# Zx81Composite.net
KiCad netlist of a schematic drawn in EAGLE
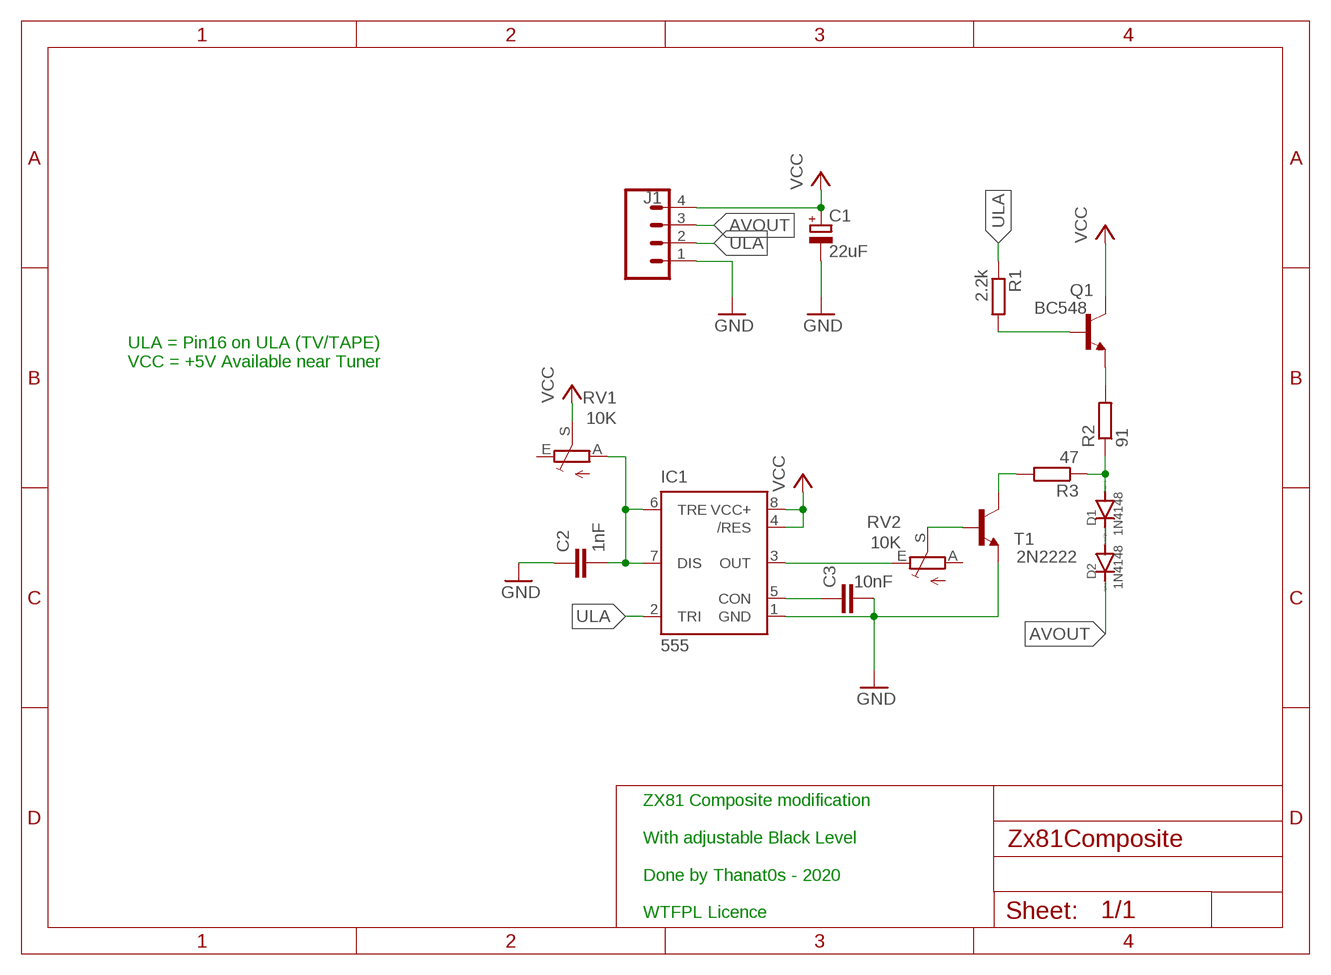
[diagram p0: schematic, sheet 1]

(export (version "E")
  (design (tool "Eeschema 10.0.6"))
  (components
    (comp (ref "C1")
      (value "22uF")
      (footprint "eagle-import:E2,5-5")
      (libsource (lib "eagle-import") (part "CPOL-EUE2.5-5"))
    )
    (comp (ref "C2")
      (value "1nF")
      (footprint "eagle-import:C025-024X044")
      (libsource (lib "eagle-import") (part "C-EU025-024X044"))
    )
    (comp (ref "C3")
      (value "10nF")
      (footprint "eagle-import:C025-024X044")
      (libsource (lib "eagle-import") (part "C-EU025-024X044"))
    )
    (comp (ref "D1")
      (value "1N4148")
      (footprint "eagle-import:DO35-7")
      (libsource (lib "eagle-import") (part "1N4148DO35-7"))
    )
    (comp (ref "D2")
      (value "1N4148")
      (footprint "eagle-import:DO35-7")
      (libsource (lib "eagle-import") (part "1N4148DO35-7"))
    )
    (comp (ref "IC1")
      (value "555")
      (footprint "eagle-import:DIP08")
      (libsource (lib "eagle-import") (part "555P"))
    )
    (comp (ref "J1")
      (value "CONN_04")
      (footprint "eagle-import:1X04")
      (libsource (lib "eagle-import") (part "CONN_04"))
    )
    (comp (ref "Q1")
      (value "BC548")
      (footprint "eagle-import:TO92-EBC")
      (libsource (lib "eagle-import") (part "BC548"))
    )
    (comp (ref "R1")
      (value "2.2k")
      (footprint "eagle-import:0207_7")
      (libsource (lib "eagle-import") (part "R-EU_0207/7"))
    )
    (comp (ref "R2")
      (value "91")
      (footprint "eagle-import:0207_7")
      (libsource (lib "eagle-import") (part "R-EU_0207/7"))
    )
    (comp (ref "R3")
      (value "47")
      (footprint "eagle-import:0207_7")
      (libsource (lib "eagle-import") (part "R-EU_0207/7"))
    )
    (comp (ref "RV1")
      (value "10K")
      (footprint "eagle-import:CA6V")
      (fields (field (name "SPICEPREFIX") "J"))
      (libsource (lib "eagle-import") (part "TRIM_EU-CA6V"))
    )
    (comp (ref "RV2")
      (value "10K")
      (footprint "eagle-import:CA6V")
      (fields (field (name "SPICEPREFIX") "J"))
      (libsource (lib "eagle-import") (part "TRIM_EU-CA6V"))
    )
    (comp (ref "T1")
      (value "2N2222")
      (footprint "eagle-import:TO92-EBC-OVAL")
      (libsource (lib "eagle-import") (part "2N2222"))
    )
  )
  (nets
    (net (code "1") (name "AVOUT") (class "Default")
      (node (ref "D2") (pin "C") (pinfunction "C_C") (pintype "passive"))
      (node (ref "J1") (pin "3") (pinfunction "3_3") (pintype "passive"))
    )
    (net (code "2") (name "GND") (class "Default")
      (node (ref "C1") (pin "-") (pinfunction "-_-") (pintype "passive"))
      (node (ref "C2") (pin "1") (pinfunction "1_1") (pintype "passive"))
      (node (ref "C3") (pin "2") (pinfunction "2_2") (pintype "passive"))
      (node (ref "IC1") (pin "1") (pinfunction "GND_1") (pintype "power_in"))
      (node (ref "J1") (pin "1") (pinfunction "1_1") (pintype "passive"))
      (node (ref "T1") (pin "E") (pinfunction "E_E") (pintype "passive"))
    )
    (net (code "3") (name "Net-(D1-PadA)") (class "Default")
      (node (ref "D1") (pin "A") (pinfunction "A_A") (pintype "passive"))
      (node (ref "R2") (pin "1") (pinfunction "1_1") (pintype "passive"))
      (node (ref "R3") (pin "1") (pinfunction "1_1") (pintype "passive"))
    )
    (net (code "4") (name "Net-(D1-PadC)") (class "Default")
      (node (ref "D1") (pin "C") (pinfunction "C_C") (pintype "passive"))
      (node (ref "D2") (pin "A") (pinfunction "A_A") (pintype "passive"))
    )
    (net (code "5") (name "Net-(IC1-CON)") (class "Default")
      (node (ref "C3") (pin "1") (pinfunction "1_1") (pintype "passive"))
      (node (ref "IC1") (pin "5") (pinfunction "CON_5") (pintype "input"))
    )
    (net (code "6") (name "Net-(IC1-DIS)") (class "Default")
      (node (ref "C2") (pin "2") (pinfunction "2_2") (pintype "passive"))
      (node (ref "IC1") (pin "6") (pinfunction "TRE_6") (pintype "input"))
      (node (ref "IC1") (pin "7") (pinfunction "DIS_7") (pintype "input"))
      (node (ref "RV1") (pin "A") (pinfunction "A_A") (pintype "passive"))
    )
    (net (code "7") (name "Net-(IC1-OUT)") (class "Default")
      (node (ref "IC1") (pin "3") (pinfunction "OUT_3") (pintype "output"))
      (node (ref "RV2") (pin "E") (pinfunction "E_E") (pintype "passive"))
    )
    (net (code "8") (name "Net-(Q1-PadB)") (class "Default")
      (node (ref "Q1") (pin "B") (pinfunction "B_B") (pintype "passive"))
      (node (ref "R1") (pin "2") (pinfunction "2_2") (pintype "passive"))
    )
    (net (code "9") (name "Net-(Q1-PadE)") (class "Default")
      (node (ref "Q1") (pin "E") (pinfunction "E_E") (pintype "passive"))
      (node (ref "R2") (pin "2") (pinfunction "2_2") (pintype "passive"))
    )
    (net (code "10") (name "Net-(R3-Pad2)") (class "Default")
      (node (ref "R3") (pin "2") (pinfunction "2_2") (pintype "passive"))
      (node (ref "T1") (pin "C") (pinfunction "C_C") (pintype "passive"))
    )
    (net (code "11") (name "Net-(RV2-PadS)") (class "Default")
      (node (ref "RV2") (pin "S") (pinfunction "S_S") (pintype "passive"))
      (node (ref "T1") (pin "B") (pinfunction "B_B") (pintype "passive"))
    )
    (net (code "12") (name "ULA") (class "Default")
      (node (ref "IC1") (pin "2") (pinfunction "TRI_2") (pintype "input"))
      (node (ref "J1") (pin "2") (pinfunction "2_2") (pintype "passive"))
      (node (ref "R1") (pin "1") (pinfunction "1_1") (pintype "passive"))
    )
    (net (code "13") (name "VCC") (class "Default")
      (node (ref "C1") (pin "+") (pinfunction "+_+") (pintype "passive"))
      (node (ref "IC1") (pin "4") (pinfunction "/RES_4") (pintype "input"))
      (node (ref "IC1") (pin "8") (pinfunction "VCC+_8") (pintype "power_in"))
      (node (ref "J1") (pin "4") (pinfunction "4_4") (pintype "passive"))
      (node (ref "Q1") (pin "C") (pinfunction "C_C") (pintype "passive"))
      (node (ref "RV1") (pin "S") (pinfunction "S_S") (pintype "passive"))
    )
    (net (code "14") (name "unconnected-(RV1-PadE)") (class "Default")
      (node (ref "RV1") (pin "E") (pinfunction "E_E") (pintype "passive"))
    )
    (net (code "15") (name "unconnected-(RV2-PadA)") (class "Default")
      (node (ref "RV2") (pin "A") (pinfunction "A_A") (pintype "passive"))
    )
  )
)
